# RAC-altimeter.net
KiCad netlist of a schematic drawn in EAGLE
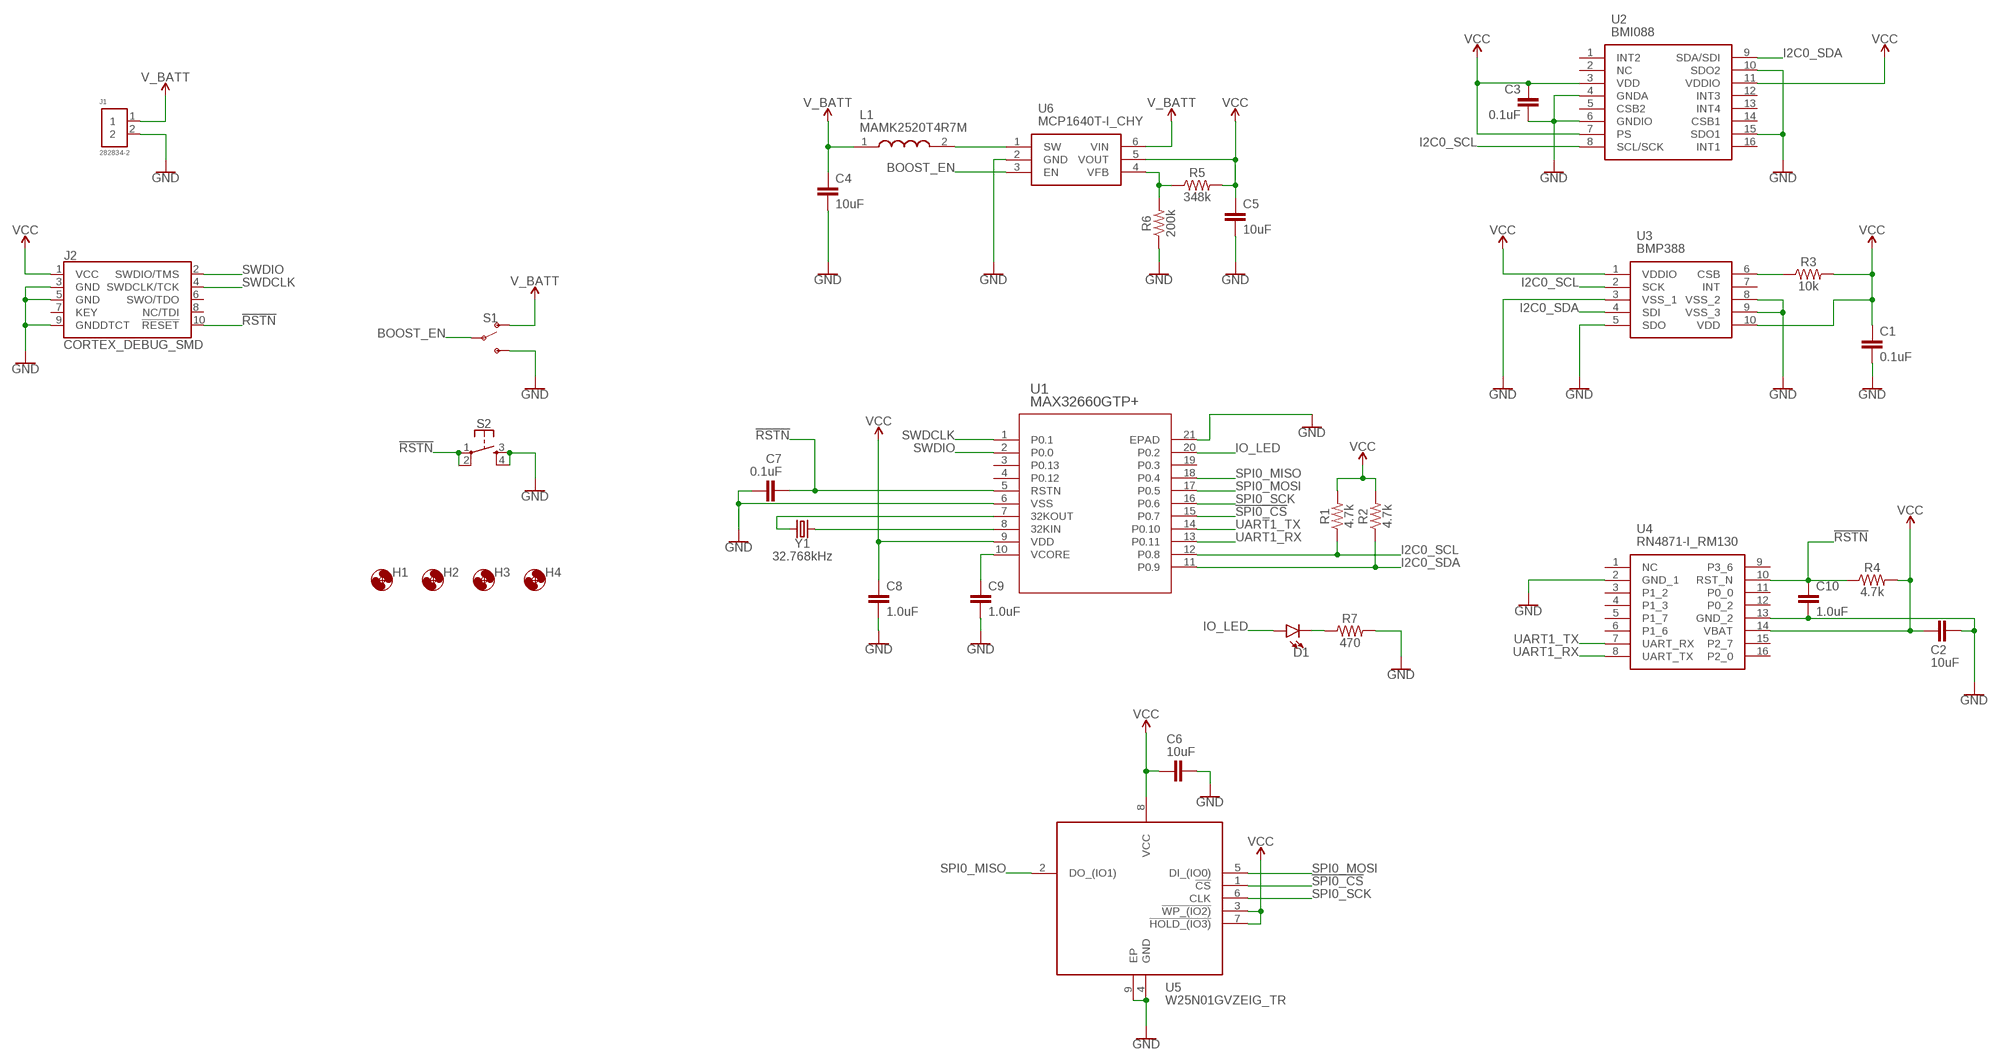
[diagram p0: schematic, sheet 1]

(export (version "E")
  (design (tool "Eeschema 10.0.6"))
  (components
    (comp (ref "C1")
      (value "0.1uF")
      (footprint "eagle-import:0603")
      (libsource (lib "eagle-import") (part "0.1UF-0603-25V-(+80/-20%)"))
    )
    (comp (ref "C2")
      (value "10uF")
      (footprint "eagle-import:0603")
      (libsource (lib "eagle-import") (part "10UF-0603-6.3V-20%"))
    )
    (comp (ref "C3")
      (value "0.1uF")
      (footprint "eagle-import:0603")
      (libsource (lib "eagle-import") (part "0.1UF-0603-25V-(+80/-20%)"))
    )
    (comp (ref "C4")
      (value "10uF")
      (footprint "eagle-import:0603")
      (libsource (lib "eagle-import") (part "10UF-0603-6.3V-20%"))
    )
    (comp (ref "C5")
      (value "10uF")
      (footprint "eagle-import:0603")
      (libsource (lib "eagle-import") (part "10UF-0603-6.3V-20%"))
    )
    (comp (ref "C6")
      (value "10uF")
      (footprint "eagle-import:0603")
      (libsource (lib "eagle-import") (part "10UF-0603-6.3V-20%"))
    )
    (comp (ref "C7")
      (value "0.1uF")
      (footprint "eagle-import:0603")
      (libsource (lib "eagle-import") (part "0.1UF-0603-25V-(+80/-20%)"))
    )
    (comp (ref "C8")
      (value "1.0uF")
      (footprint "eagle-import:0603")
      (libsource (lib "eagle-import") (part "1.0UF-0603-16V-10%"))
    )
    (comp (ref "C9")
      (value "1.0uF")
      (footprint "eagle-import:0603")
      (libsource (lib "eagle-import") (part "1.0UF-0603-16V-10%"))
    )
    (comp (ref "C10")
      (value "1.0uF")
      (footprint "eagle-import:0603")
      (libsource (lib "eagle-import") (part "1.0UF-0603-16V-10%"))
    )
    (comp (ref "D1")
      (value "LED0603")
      (footprint "eagle-import:LED-0603")
      (libsource (lib "eagle-import") (part "LED0603"))
    )
    (comp (ref "H1")
      (value "MOUNT-HOLE2.8")
      (footprint "eagle-import:2,8")
      (libsource (lib "eagle-import") (part "MOUNT-HOLE2.8"))
    )
    (comp (ref "H2")
      (value "MOUNT-HOLE2.8")
      (footprint "eagle-import:2,8")
      (libsource (lib "eagle-import") (part "MOUNT-HOLE2.8"))
    )
    (comp (ref "H3")
      (value "MOUNT-HOLE2.8")
      (footprint "eagle-import:2,8")
      (libsource (lib "eagle-import") (part "MOUNT-HOLE2.8"))
    )
    (comp (ref "H4")
      (value "MOUNT-HOLE2.8")
      (footprint "eagle-import:2,8")
      (libsource (lib "eagle-import") (part "MOUNT-HOLE2.8"))
    )
    (comp (ref "J1")
      (value "282834-2")
      (footprint "eagle-import:CONN_282834-2")
      (fields (field (name "DIGI-KEY_PART_NUMBER") "A98333-ND") (field (name "MF") "TE Connectivity"))
      (libsource (lib "eagle-import") (part "282834-2"))
    )
    (comp (ref "J2")
      (value "CORTEX_DEBUG_SMD")
      (footprint "eagle-import:SAMTECH_FTSH-105-01")
      (libsource (lib "eagle-import") (part "CORTEX_DEBUG_SMD"))
    )
    (comp (ref "L1")
      (value "MAMK2520T4R7M")
      (footprint "eagle-import:INDM2520X120N")
      (libsource (lib "eagle-import") (part "MAMK2520T4R7M"))
    )
    (comp (ref "R1")
      (value "4.7k")
      (footprint "eagle-import:0603")
      (libsource (lib "eagle-import") (part "4.7KOHM-0603-1/10W-1%"))
    )
    (comp (ref "R2")
      (value "4.7k")
      (footprint "eagle-import:0603")
      (libsource (lib "eagle-import") (part "4.7KOHM-0603-1/10W-1%"))
    )
    (comp (ref "R3")
      (value "10k")
      (footprint "eagle-import:0603")
      (libsource (lib "eagle-import") (part "10KOHM-0603-1/10W-1%"))
    )
    (comp (ref "R4")
      (value "4.7k")
      (footprint "eagle-import:0603")
      (libsource (lib "eagle-import") (part "4.7KOHM-0603-1/10W-1%"))
    )
    (comp (ref "R5")
      (value "348k")
      (footprint "eagle-import:0603")
      (libsource (lib "eagle-import") (part "348KOHM-0603-1/10W-1%"))
    )
    (comp (ref "R6")
      (value "200k")
      (footprint "eagle-import:0603")
      (libsource (lib "eagle-import") (part "200KOHM-0603-1/10W-1%"))
    )
    (comp (ref "R7")
      (value "470")
      (footprint "eagle-import:0603")
      (libsource (lib "eagle-import") (part "470OHM-0603-1/10W-1%"))
    )
    (comp (ref "S1")
      (value "SWITCH-SPDT-SMD-AYZ0202")
      (footprint "eagle-import:SWITCH_DPDT_SMD_AYZ0202")
      (libsource (lib "eagle-import") (part "SWITCH-SPDT-SMD-AYZ0202"))
    )
    (comp (ref "S2")
      (value "MOMENTARY-SWITCH-SPST-2-SMD-4.6X2.8MM")
      (footprint "eagle-import:TACTILE_SWITCH_SMD_4.6X2.8MM")
      (libsource (lib "eagle-import") (part "MOMENTARY-SWITCH-SPST-2-SMD-4.6X2.8MM"))
    )
    (comp (ref "U1")
      (value "MAX32660GTP+")
      (footprint "eagle-import:21-0139V_T2044+5")
      (libsource (lib "eagle-import") (part "MAX32660GTP+"))
    )
    (comp (ref "U2")
      (value "BMI088")
      (footprint "eagle-import:BMI088")
      (fields (field (name "MOUSER_PART_NUMBER") "262-BMI088"))
      (libsource (lib "eagle-import") (part "BMI088"))
    )
    (comp (ref "U3")
      (value "BMP388")
      (footprint "eagle-import:BMP388")
      (fields (field (name "MOUSER_PART_NUMBER") "262-BMP388"))
      (libsource (lib "eagle-import") (part "BMP388"))
    )
    (comp (ref "U4")
      (value "RN4871-I_RM130")
      (footprint "eagle-import:RN4871")
      (fields
        (field (name "MANUFACTURER_PART_NUMBER") "RN4871-I/RM130")
        (field (name "MOUSER_PART_NUMBER") "579-RN4871IRM130")
      )
      (libsource (lib "eagle-import") (part "RN4871-I_RM130"))
    )
    (comp (ref "U5")
      (value "W25N01GVZEIG_TR")
      (footprint "eagle-import:SON127P800X600X80-9N")
      (fields
        (field (name "MANUFACTURER_PART_NUMBER") "W25N01GVZEIG TR")
        (field (name "MOUSER_PART_NUMBER") "454-W25N01GVZEIGTR")
      )
      (libsource (lib "eagle-import") (part "W25N01GVZEIG_TR"))
    )
    (comp (ref "U6")
      (value "MCP1640T-I_CHY")
      (footprint "eagle-import:SOT95P270X145-6N")
      (fields
        (field (name "MANUFACTURER_PART_NUMBER") "MCP1640T-I/CHY")
        (field (name "MOUSER_PART_NUMBER") "579-MCP1640TI/CHY")
      )
      (libsource (lib "eagle-import") (part "MCP1640T-I_CHY"))
    )
    (comp (ref "Y1")
      (value "32.768kHz")
      (footprint "eagle-import:CRYSTAL-SMD-3.2X1.5MM")
      (libsource (lib "eagle-import") (part "CRYSTAL-32.768KHZSMD-3.2X1.5"))
    )
  )
  (nets
    (net (code "1") (name "/BOOST_EN") (class "Default")
      (node (ref "S1") (pin "2") (pinfunction "P_2") (pintype "passive"))
      (node (ref "U6") (pin "3") (pinfunction "EN_3") (pintype "bidirectional"))
    )
    (net (code "2") (name "/I2C0_SCL") (class "Default")
      (node (ref "R1") (pin "1") (pinfunction "1_1") (pintype "passive"))
      (node (ref "U1") (pin "12") (pinfunction "P0.8_12") (pintype "bidirectional"))
      (node (ref "U2") (pin "8") (pinfunction "SCL/SCK_8") (pintype "bidirectional"))
      (node (ref "U3") (pin "2") (pinfunction "SCK_2") (pintype "bidirectional"))
    )
    (net (code "3") (name "/I2C0_SDA") (class "Default")
      (node (ref "R2") (pin "1") (pinfunction "1_1") (pintype "passive"))
      (node (ref "U1") (pin "11") (pinfunction "P0.9_11") (pintype "bidirectional"))
      (node (ref "U2") (pin "9") (pinfunction "SDA/SDI_9") (pintype "bidirectional"))
      (node (ref "U3") (pin "4") (pinfunction "SDI_4") (pintype "bidirectional"))
    )
    (net (code "4") (name "/IO_LED") (class "Default")
      (node (ref "D1") (pin "A") (pinfunction "A_A") (pintype "passive"))
      (node (ref "U1") (pin "20") (pinfunction "P0.2_20") (pintype "bidirectional"))
    )
    (net (code "5") (name "/SPI0_MISO") (class "Default")
      (node (ref "U1") (pin "18") (pinfunction "P0.4_18") (pintype "bidirectional"))
      (node (ref "U5") (pin "2") (pinfunction "DO_(IO1)_2") (pintype "bidirectional"))
    )
    (net (code "6") (name "/SPI0_MOSI") (class "Default")
      (node (ref "U1") (pin "17") (pinfunction "P0.5_17") (pintype "bidirectional"))
      (node (ref "U5") (pin "5") (pinfunction "DI_(IO0)_5") (pintype "bidirectional"))
    )
    (net (code "7") (name "/SPI0_SCK") (class "Default")
      (node (ref "U1") (pin "16") (pinfunction "P0.6_16") (pintype "bidirectional"))
      (node (ref "U5") (pin "6") (pinfunction "CLK_6") (pintype "bidirectional"))
    )
    (net (code "8") (name "/SWDCLK") (class "Default")
      (node (ref "J2") (pin "4") (pinfunction "SWDCLK/TCK_4") (pintype "bidirectional"))
      (node (ref "U1") (pin "1") (pinfunction "P0.1_1") (pintype "bidirectional"))
    )
    (net (code "9") (name "/SWDIO") (class "Default")
      (node (ref "J2") (pin "2") (pinfunction "SWDIO/TMS_2") (pintype "bidirectional"))
      (node (ref "U1") (pin "2") (pinfunction "P0.0_2") (pintype "bidirectional"))
    )
    (net (code "10") (name "/UART1_RX") (class "Default")
      (node (ref "U1") (pin "13") (pinfunction "P0.11_13") (pintype "bidirectional"))
      (node (ref "U4") (pin "8") (pinfunction "UART_TX_8") (pintype "bidirectional"))
    )
    (net (code "11") (name "/UART1_TX") (class "Default")
      (node (ref "U1") (pin "14") (pinfunction "P0.10_14") (pintype "bidirectional"))
      (node (ref "U4") (pin "7") (pinfunction "UART_RX_7") (pintype "bidirectional"))
    )
    (net (code "12") (name "/~{RSTN}") (class "Default")
      (node (ref "C10") (pin "1") (pinfunction "1_1") (pintype "passive"))
      (node (ref "C7") (pin "1") (pinfunction "1_1") (pintype "passive"))
      (node (ref "J2") (pin "10") (pinfunction "~{RESET}_10") (pintype "bidirectional"))
      (node (ref "R4") (pin "1") (pinfunction "1_1") (pintype "passive"))
      (node (ref "S2") (pin "1") (pinfunction "1_1") (pintype "passive"))
      (node (ref "S2") (pin "2") (pinfunction "2_2") (pintype "passive"))
      (node (ref "U1") (pin "5") (pinfunction "RSTN_5") (pintype "passive"))
      (node (ref "U4") (pin "10") (pinfunction "RST_N_10") (pintype "bidirectional"))
    )
    (net (code "13") (name "/~{SPI0_CS}") (class "Default")
      (node (ref "U1") (pin "15") (pinfunction "P0.7_15") (pintype "bidirectional"))
      (node (ref "U5") (pin "1") (pinfunction "~{CS}_1") (pintype "bidirectional"))
    )
    (net (code "14") (name "GND") (class "Default")
      (node (ref "C1") (pin "2") (pinfunction "2_2") (pintype "passive"))
      (node (ref "C10") (pin "2") (pinfunction "2_2") (pintype "passive"))
      (node (ref "C2") (pin "2") (pinfunction "2_2") (pintype "passive"))
      (node (ref "C3") (pin "2") (pinfunction "2_2") (pintype "passive"))
      (node (ref "C4") (pin "2") (pinfunction "2_2") (pintype "passive"))
      (node (ref "C5") (pin "2") (pinfunction "2_2") (pintype "passive"))
      (node (ref "C6") (pin "2") (pinfunction "2_2") (pintype "passive"))
      (node (ref "C7") (pin "2") (pinfunction "2_2") (pintype "passive"))
      (node (ref "C8") (pin "2") (pinfunction "2_2") (pintype "passive"))
      (node (ref "C9") (pin "2") (pinfunction "2_2") (pintype "passive"))
      (node (ref "J1") (pin "2") (pinfunction "2_2") (pintype "passive"))
      (node (ref "J2") (pin "3") (pinfunction "GND_3") (pintype "bidirectional"))
      (node (ref "J2") (pin "5") (pinfunction "GND_5") (pintype "bidirectional"))
      (node (ref "J2") (pin "9") (pinfunction "GNDDTCT_9") (pintype "bidirectional"))
      (node (ref "R6") (pin "1") (pinfunction "1_1") (pintype "passive"))
      (node (ref "R7") (pin "2") (pinfunction "2_2") (pintype "passive"))
      (node (ref "S1") (pin "3") (pinfunction "S_3") (pintype "passive"))
      (node (ref "S2") (pin "3") (pinfunction "3_3") (pintype "passive"))
      (node (ref "S2") (pin "4") (pinfunction "4_4") (pintype "passive"))
      (node (ref "U1") (pin "21") (pinfunction "EPAD_21") (pintype "passive"))
      (node (ref "U1") (pin "6") (pinfunction "VSS_6") (pintype "passive"))
      (node (ref "U2") (pin "10") (pinfunction "SDO2_10") (pintype "bidirectional"))
      (node (ref "U2") (pin "15") (pinfunction "SDO1_15") (pintype "bidirectional"))
      (node (ref "U2") (pin "4") (pinfunction "GNDA_4") (pintype "bidirectional"))
      (node (ref "U2") (pin "6") (pinfunction "GNDIO_6") (pintype "bidirectional"))
      (node (ref "U3") (pin "3") (pinfunction "VSS_1_3") (pintype "bidirectional"))
      (node (ref "U3") (pin "5") (pinfunction "SDO_5") (pintype "bidirectional"))
      (node (ref "U3") (pin "8") (pinfunction "VSS_2_8") (pintype "bidirectional"))
      (node (ref "U3") (pin "9") (pinfunction "VSS_3_9") (pintype "bidirectional"))
      (node (ref "U4") (pin "13") (pinfunction "GND_2_13") (pintype "bidirectional"))
      (node (ref "U4") (pin "2") (pinfunction "GND_1_2") (pintype "bidirectional"))
      (node (ref "U5") (pin "4") (pinfunction "GND_4") (pintype "bidirectional"))
      (node (ref "U5") (pin "9") (pinfunction "EP_9") (pintype "bidirectional"))
      (node (ref "U6") (pin "2") (pinfunction "GND_2") (pintype "power_in"))
    )
    (net (code "15") (name "Net-(D1-PadC)") (class "Default")
      (node (ref "D1") (pin "C") (pinfunction "C_C") (pintype "passive"))
      (node (ref "R7") (pin "1") (pinfunction "1_1") (pintype "passive"))
    )
    (net (code "16") (name "Net-(U1-32KIN)") (class "Default")
      (node (ref "U1") (pin "8") (pinfunction "32KIN_8") (pintype "bidirectional"))
      (node (ref "Y1") (pin "P$1") (pinfunction "1_P$1") (pintype "passive"))
    )
    (net (code "17") (name "Net-(U1-32KOUT)") (class "Default")
      (node (ref "U1") (pin "7") (pinfunction "32KOUT_7") (pintype "output"))
      (node (ref "Y1") (pin "P$2") (pinfunction "2_P$2") (pintype "passive"))
    )
    (net (code "18") (name "Net-(U1-VCORE)") (class "Default")
      (node (ref "C9") (pin "1") (pinfunction "1_1") (pintype "passive"))
      (node (ref "U1") (pin "10") (pinfunction "VCORE_10") (pintype "passive"))
    )
    (net (code "19") (name "Net-(U3-CSB)") (class "Default")
      (node (ref "R3") (pin "1") (pinfunction "1_1") (pintype "passive"))
      (node (ref "U3") (pin "6") (pinfunction "CSB_6") (pintype "bidirectional"))
    )
    (net (code "20") (name "Net-(U6-SW)") (class "Default")
      (node (ref "L1") (pin "2") (pinfunction "2_2") (pintype "bidirectional"))
      (node (ref "U6") (pin "1") (pinfunction "SW_1") (pintype "bidirectional"))
    )
    (net (code "21") (name "Net-(U6-VFB)") (class "Default")
      (node (ref "R5") (pin "1") (pinfunction "1_1") (pintype "passive"))
      (node (ref "R6") (pin "2") (pinfunction "2_2") (pintype "passive"))
      (node (ref "U6") (pin "4") (pinfunction "VFB_4") (pintype "bidirectional"))
    )
    (net (code "22") (name "VCC") (class "Default")
      (node (ref "C1") (pin "1") (pinfunction "1_1") (pintype "passive"))
      (node (ref "C2") (pin "1") (pinfunction "1_1") (pintype "passive"))
      (node (ref "C3") (pin "1") (pinfunction "1_1") (pintype "passive"))
      (node (ref "C5") (pin "1") (pinfunction "1_1") (pintype "passive"))
      (node (ref "C6") (pin "1") (pinfunction "1_1") (pintype "passive"))
      (node (ref "C8") (pin "1") (pinfunction "1_1") (pintype "passive"))
      (node (ref "J2") (pin "1") (pinfunction "VCC_1") (pintype "bidirectional"))
      (node (ref "R1") (pin "2") (pinfunction "2_2") (pintype "passive"))
      (node (ref "R2") (pin "2") (pinfunction "2_2") (pintype "passive"))
      (node (ref "R3") (pin "2") (pinfunction "2_2") (pintype "passive"))
      (node (ref "R4") (pin "2") (pinfunction "2_2") (pintype "passive"))
      (node (ref "R5") (pin "2") (pinfunction "2_2") (pintype "passive"))
      (node (ref "U1") (pin "9") (pinfunction "VDD_9") (pintype "power_in"))
      (node (ref "U2") (pin "11") (pinfunction "VDDIO_11") (pintype "bidirectional"))
      (node (ref "U2") (pin "3") (pinfunction "VDD_3") (pintype "bidirectional"))
      (node (ref "U2") (pin "7") (pinfunction "PS_7") (pintype "bidirectional"))
      (node (ref "U3") (pin "1") (pinfunction "VDDIO_1") (pintype "bidirectional"))
      (node (ref "U3") (pin "10") (pinfunction "VDD_10") (pintype "bidirectional"))
      (node (ref "U4") (pin "14") (pinfunction "VBAT_14") (pintype "bidirectional"))
      (node (ref "U5") (pin "3") (pinfunction "~{WP_(IO2})_3") (pintype "bidirectional"))
      (node (ref "U5") (pin "7") (pinfunction "~{HOLD_(IO3})_7") (pintype "bidirectional"))
      (node (ref "U5") (pin "8") (pinfunction "VCC_8") (pintype "bidirectional"))
      (node (ref "U6") (pin "5") (pinfunction "VOUT_5") (pintype "output"))
    )
    (net (code "23") (name "V_BATT") (class "Default")
      (node (ref "C4") (pin "1") (pinfunction "1_1") (pintype "passive"))
      (node (ref "J1") (pin "1") (pinfunction "1_1") (pintype "passive"))
      (node (ref "L1") (pin "1") (pinfunction "1_1") (pintype "bidirectional"))
      (node (ref "S1") (pin "1") (pinfunction "O_1") (pintype "passive"))
      (node (ref "U6") (pin "6") (pinfunction "VIN_6") (pintype "input"))
    )
    (net (code "24") (name "unconnected-(J2-KEY-Pad7)") (class "Default")
      (node (ref "J2") (pin "7") (pinfunction "KEY_7") (pintype "bidirectional"))
    )
    (net (code "25") (name "unconnected-(J2-NC{slash}TDI-Pad8)") (class "Default")
      (node (ref "J2") (pin "8") (pinfunction "NC/TDI_8") (pintype "bidirectional"))
    )
    (net (code "26") (name "unconnected-(J2-SWO{slash}TDO-Pad6)") (class "Default")
      (node (ref "J2") (pin "6") (pinfunction "SWO/TDO_6") (pintype "bidirectional"))
    )
    (net (code "27") (name "unconnected-(U1-P0.3-Pad19)") (class "Default")
      (node (ref "U1") (pin "19") (pinfunction "P0.3_19") (pintype "bidirectional"))
    )
    (net (code "28") (name "unconnected-(U1-P0.12-Pad4)") (class "Default")
      (node (ref "U1") (pin "4") (pinfunction "P0.12_4") (pintype "bidirectional"))
    )
    (net (code "29") (name "unconnected-(U1-P0.13-Pad3)") (class "Default")
      (node (ref "U1") (pin "3") (pinfunction "P0.13_3") (pintype "bidirectional"))
    )
    (net (code "30") (name "unconnected-(U2-CSB1-Pad14)") (class "Default")
      (node (ref "U2") (pin "14") (pinfunction "CSB1_14") (pintype "bidirectional"))
    )
    (net (code "31") (name "unconnected-(U2-CSB2-Pad5)") (class "Default")
      (node (ref "U2") (pin "5") (pinfunction "CSB2_5") (pintype "bidirectional"))
    )
    (net (code "32") (name "unconnected-(U2-INT1-Pad16)") (class "Default")
      (node (ref "U2") (pin "16") (pinfunction "INT1_16") (pintype "bidirectional"))
    )
    (net (code "33") (name "unconnected-(U2-INT2-Pad1)") (class "Default")
      (node (ref "U2") (pin "1") (pinfunction "INT2_1") (pintype "bidirectional"))
    )
    (net (code "34") (name "unconnected-(U2-INT3-Pad12)") (class "Default")
      (node (ref "U2") (pin "12") (pinfunction "INT3_12") (pintype "bidirectional"))
    )
    (net (code "35") (name "unconnected-(U2-INT4-Pad13)") (class "Default")
      (node (ref "U2") (pin "13") (pinfunction "INT4_13") (pintype "bidirectional"))
    )
    (net (code "36") (name "unconnected-(U2-NC-Pad2)") (class "Default")
      (node (ref "U2") (pin "2") (pinfunction "NC_2") (pintype "no_connect"))
    )
    (net (code "37") (name "unconnected-(U3-INT-Pad7)") (class "Default")
      (node (ref "U3") (pin "7") (pinfunction "INT_7") (pintype "bidirectional"))
    )
    (net (code "38") (name "unconnected-(U4-NC-Pad1)") (class "Default")
      (node (ref "U4") (pin "1") (pinfunction "NC_1") (pintype "no_connect"))
    )
    (net (code "39") (name "unconnected-(U4-P0_0-Pad11)") (class "Default")
      (node (ref "U4") (pin "11") (pinfunction "P0_0_11") (pintype "bidirectional"))
    )
    (net (code "40") (name "unconnected-(U4-P0_2-Pad12)") (class "Default")
      (node (ref "U4") (pin "12") (pinfunction "P0_2_12") (pintype "bidirectional"))
    )
    (net (code "41") (name "unconnected-(U4-P1_2-Pad3)") (class "Default")
      (node (ref "U4") (pin "3") (pinfunction "P1_2_3") (pintype "bidirectional"))
    )
    (net (code "42") (name "unconnected-(U4-P1_3-Pad4)") (class "Default")
      (node (ref "U4") (pin "4") (pinfunction "P1_3_4") (pintype "bidirectional"))
    )
    (net (code "43") (name "unconnected-(U4-P1_6-Pad6)") (class "Default")
      (node (ref "U4") (pin "6") (pinfunction "P1_6_6") (pintype "bidirectional"))
    )
    (net (code "44") (name "unconnected-(U4-P1_7-Pad5)") (class "Default")
      (node (ref "U4") (pin "5") (pinfunction "P1_7_5") (pintype "bidirectional"))
    )
    (net (code "45") (name "unconnected-(U4-P2_0-Pad16)") (class "Default")
      (node (ref "U4") (pin "16") (pinfunction "P2_0_16") (pintype "bidirectional"))
    )
    (net (code "46") (name "unconnected-(U4-P2_7-Pad15)") (class "Default")
      (node (ref "U4") (pin "15") (pinfunction "P2_7_15") (pintype "bidirectional"))
    )
    (net (code "47") (name "unconnected-(U4-P3_6-Pad9)") (class "Default")
      (node (ref "U4") (pin "9") (pinfunction "P3_6_9") (pintype "bidirectional"))
    )
  )
)
